# LineCliffSensors.net
KiCad netlist of a schematic drawn in Altium Designer
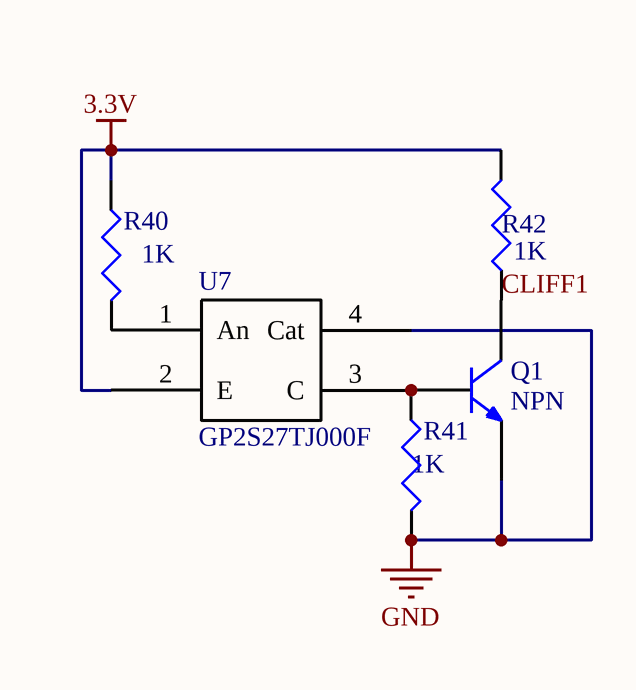
[diagram p0: LineCliffSensors.SchDoc]

(export (version "E")
  (design (tool "Eeschema 10.0.6"))
  (components
    (comp (ref "Q1") (value "NPN") (footprint "SOT-23") (libsource (lib "mrone") (part "NPN")))
    (comp (ref "R40")
      (value "1K")
      (footprint "RESC1608L")
      (description "Resistor")
      (fields (field (name "Comment") "Res3") (field (name "PUBLISHER") "Altium Limited"))
      (libsource (lib "Miscellaneous Devices") (part "Res3"))
    )
    (comp (ref "R41")
      (value "1K")
      (footprint "RESC1608L")
      (description "Resistor")
      (fields (field (name "Comment") "Res3") (field (name "PUBLISHER") "Altium Limited"))
      (libsource (lib "Miscellaneous Devices") (part "Res3"))
    )
    (comp (ref "R42")
      (value "1K")
      (footprint "RESC1608L")
      (description "Resistor")
      (fields (field (name "Comment") "Res3") (field (name "PUBLISHER") "Altium Limited"))
      (libsource (lib "Miscellaneous Devices") (part "Res3"))
    )
    (comp (ref "U7")
      (value "GP2S27TJ000F")
      (footprint "GP2S27J0000F")
      (libsource (lib "mrone") (part "GP2S27TJ000F"))
    )
  )
  (nets
    (net (code "1") (name "/CLIFF1") (class "Default")
      (node (ref "Q1") (pin "3") (pinfunction "C_3") (pintype "passive"))
      (node (ref "R42") (pin "1") (pinfunction "1_1") (pintype "passive"))
    )
    (net (code "2") (name "3.3V") (class "Default")
      (node (ref "R40") (pin "1") (pinfunction "1_1") (pintype "passive"))
      (node (ref "R42") (pin "2") (pinfunction "2_2") (pintype "passive"))
      (node (ref "U7") (pin "2") (pinfunction "E_2") (pintype "passive"))
    )
    (net (code "3") (name "GND") (class "Default")
      (node (ref "Q1") (pin "2") (pinfunction "E_2") (pintype "passive"))
      (node (ref "R41") (pin "2") (pinfunction "2_2") (pintype "passive"))
      (node (ref "U7") (pin "4") (pinfunction "Cat_4") (pintype "passive"))
    )
    (net (code "4") (name "Net-(Q1-B)") (class "Default")
      (node (ref "Q1") (pin "1") (pinfunction "B_1") (pintype "passive"))
      (node (ref "R41") (pin "1") (pinfunction "1_1") (pintype "passive"))
      (node (ref "U7") (pin "3") (pinfunction "C_3") (pintype "passive"))
    )
    (net (code "5") (name "Net-(U7-An)") (class "Default")
      (node (ref "R40") (pin "2") (pinfunction "2_2") (pintype "passive"))
      (node (ref "U7") (pin "1") (pinfunction "An_1") (pintype "passive"))
    )
  )
)
